# microm_schem2.net
KiCad netlist of a schematic drawn in EAGLE
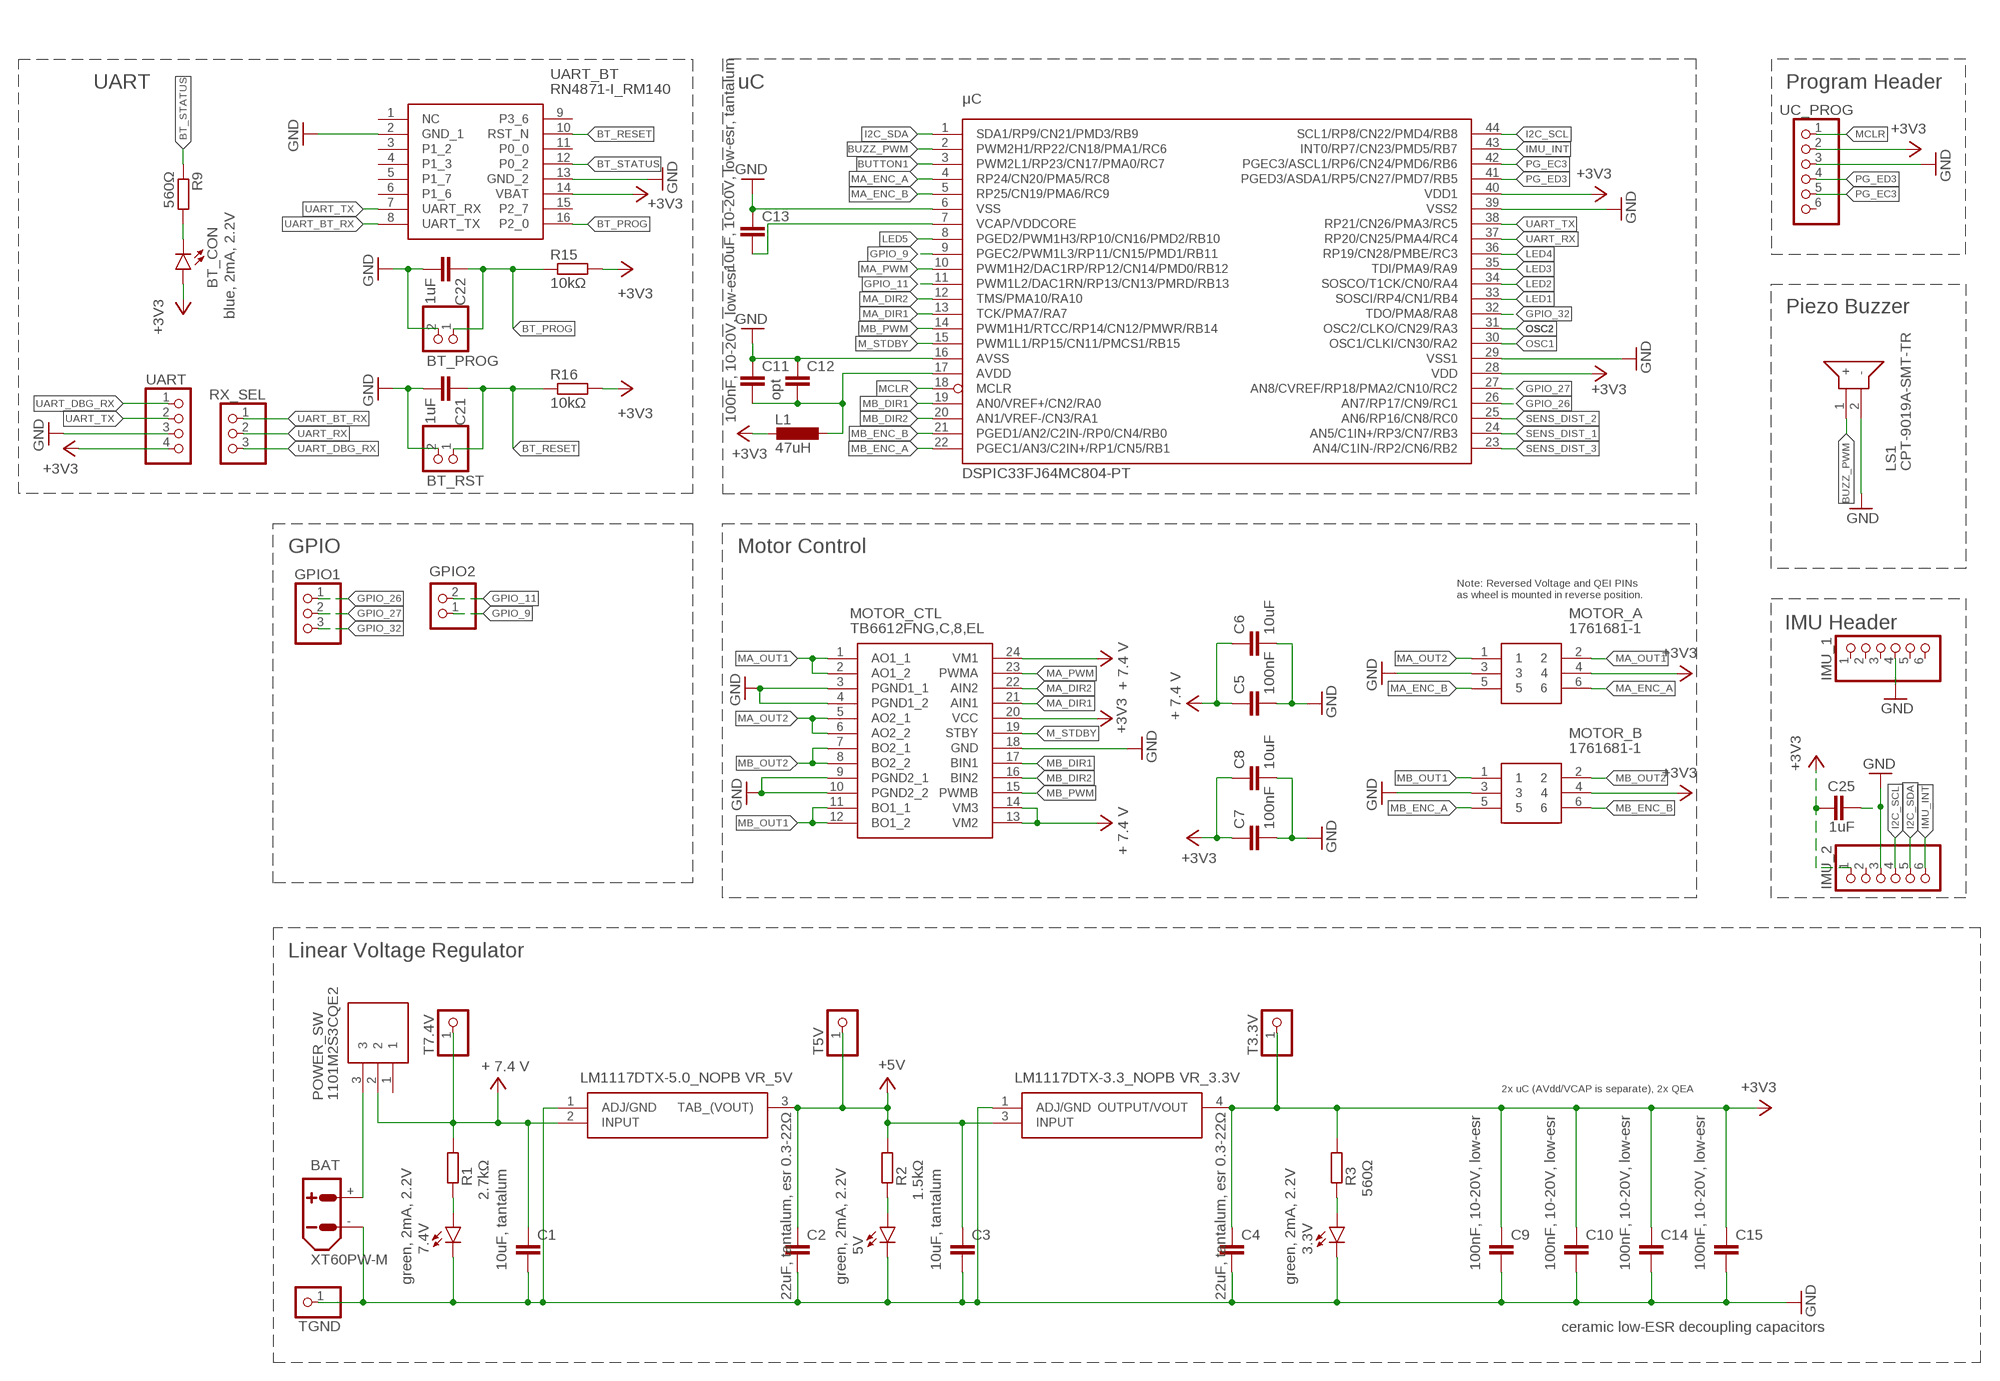
[diagram p0: schematic, sheet 1, part 1 of 2]
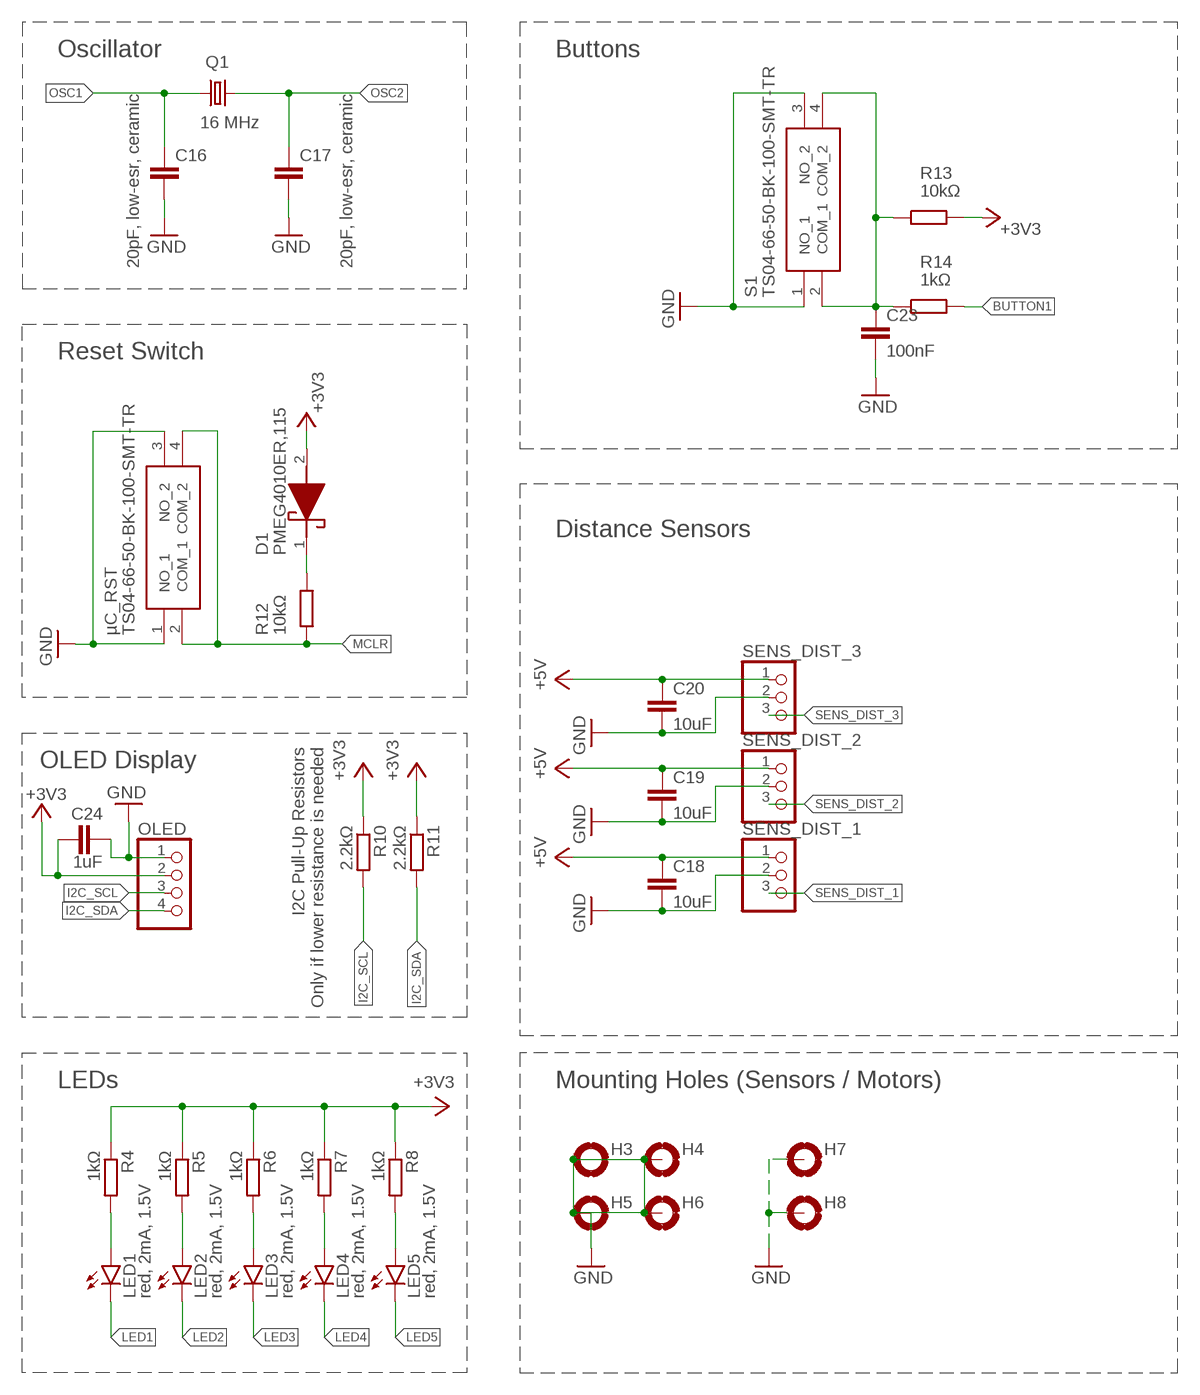
[diagram p1: schematic, sheet 1, part 2 of 2]

(export (version "E")
  (design (tool "Eeschema 10.0.6"))
  (components
    (comp (ref "3.3V")
      (value "green, 2mA, 2.2V")
      (footprint "eagle-import:CHIP-LED0805")
      (libsource (lib "eagle-import") (part "LEDCHIP-LED0805"))
    )
    (comp (ref "5V")
      (value "green, 2mA, 2.2V")
      (footprint "eagle-import:CHIP-LED0805")
      (libsource (lib "eagle-import") (part "LEDCHIP-LED0805"))
    )
    (comp (ref "7.4V")
      (value "green, 2mA, 2.2V")
      (footprint "eagle-import:CHIP-LED0805")
      (libsource (lib "eagle-import") (part "LEDCHIP-LED0805"))
    )
    (comp (ref "BAT")
      (value "XT60PW-M")
      (footprint "eagle-import:XT60PW-M")
      (libsource (lib "eagle-import") (part "XT60PW-M"))
    )
    (comp (ref "BT_CON")
      (value "blue, 2mA, 2.2V")
      (footprint "eagle-import:CHIP-LED0805")
      (libsource (lib "eagle-import") (part "LEDCHIP-LED0805"))
    )
    (comp (ref "BT_PROG")
      (value "PINHD-1X2")
      (footprint "eagle-import:1X02")
      (libsource (lib "eagle-import") (part "PINHD-1X2"))
    )
    (comp (ref "BT_RST")
      (value "PINHD-1X2")
      (footprint "eagle-import:1X02")
      (libsource (lib "eagle-import") (part "PINHD-1X2"))
    )
    (comp (ref "C1")
      (value "10uF, tantalum")
      (footprint "eagle-import:C0805")
      (libsource (lib "eagle-import") (part "C-EUC0805"))
    )
    (comp (ref "C2")
      (value "22uF, tantalum, esr 0.3-22Ω")
      (footprint "eagle-import:C0805")
      (libsource (lib "eagle-import") (part "C-EUC0805"))
    )
    (comp (ref "C3")
      (value "10uF, tantalum")
      (footprint "eagle-import:C0805")
      (libsource (lib "eagle-import") (part "C-EUC0805"))
    )
    (comp (ref "C4")
      (value "22uF, tantalum, esr 0.3-22Ω")
      (footprint "eagle-import:C0805")
      (libsource (lib "eagle-import") (part "C-EUC0805"))
    )
    (comp (ref "C5")
      (value "100nF")
      (footprint "eagle-import:C0805")
      (libsource (lib "eagle-import") (part "C-EUC0805"))
    )
    (comp (ref "C6")
      (value "10uF")
      (footprint "eagle-import:C0805")
      (libsource (lib "eagle-import") (part "C-EUC0805"))
    )
    (comp (ref "C7")
      (value "100nF")
      (footprint "eagle-import:C0805")
      (libsource (lib "eagle-import") (part "C-EUC0805"))
    )
    (comp (ref "C8")
      (value "10uF")
      (footprint "eagle-import:C0805")
      (libsource (lib "eagle-import") (part "C-EUC0805"))
    )
    (comp (ref "C9")
      (value "100nF, 10-20V, low-esr")
      (footprint "eagle-import:C0805")
      (libsource (lib "eagle-import") (part "C-EUC0805"))
    )
    (comp (ref "C10")
      (value "100nF, 10-20V, low-esr")
      (footprint "eagle-import:C0805")
      (libsource (lib "eagle-import") (part "C-EUC0805"))
    )
    (comp (ref "C11")
      (value "100nF, 10-20V, low-esr")
      (footprint "eagle-import:C0805")
      (libsource (lib "eagle-import") (part "C-EUC0805"))
    )
    (comp (ref "C12")
      (value "opt")
      (footprint "eagle-import:C0805")
      (libsource (lib "eagle-import") (part "C-EUC0805"))
    )
    (comp (ref "C13")
      (value "10uF, 10-20V, low-esr, tantalum")
      (footprint "eagle-import:C0805")
      (libsource (lib "eagle-import") (part "C-EUC0805"))
    )
    (comp (ref "C14")
      (value "100nF, 10-20V, low-esr")
      (footprint "eagle-import:C0805")
      (libsource (lib "eagle-import") (part "C-EUC0805"))
    )
    (comp (ref "C15")
      (value "100nF, 10-20V, low-esr")
      (footprint "eagle-import:C0805")
      (libsource (lib "eagle-import") (part "C-EUC0805"))
    )
    (comp (ref "C16")
      (value "20pF, low-esr, ceramic")
      (footprint "eagle-import:C0805")
      (libsource (lib "eagle-import") (part "C-EUC0805"))
    )
    (comp (ref "C17")
      (value "20pF, low-esr, ceramic")
      (footprint "eagle-import:C0805")
      (libsource (lib "eagle-import") (part "C-EUC0805"))
    )
    (comp (ref "C18")
      (value "10uF")
      (footprint "eagle-import:C0805")
      (libsource (lib "eagle-import") (part "C-EUC0805"))
    )
    (comp (ref "C19")
      (value "10uF")
      (footprint "eagle-import:C0805")
      (libsource (lib "eagle-import") (part "C-EUC0805"))
    )
    (comp (ref "C20")
      (value "10uF")
      (footprint "eagle-import:C0805")
      (libsource (lib "eagle-import") (part "C-EUC0805"))
    )
    (comp (ref "C21")
      (value "1uF")
      (footprint "eagle-import:C0805")
      (libsource (lib "eagle-import") (part "C-EUC0805"))
    )
    (comp (ref "C22")
      (value "1uF")
      (footprint "eagle-import:C0805")
      (libsource (lib "eagle-import") (part "C-EUC0805"))
    )
    (comp (ref "C23")
      (value "100nF")
      (footprint "eagle-import:C0805")
      (libsource (lib "eagle-import") (part "C-EUC0805"))
    )
    (comp (ref "C24")
      (value "1uF")
      (footprint "eagle-import:C0805")
      (libsource (lib "eagle-import") (part "C-EUC0805"))
    )
    (comp (ref "C25")
      (value "1uF")
      (footprint "eagle-import:C0805")
      (libsource (lib "eagle-import") (part "C-EUC0805"))
    )
    (comp (ref "D1")
      (value "PMEG4010ER,115")
      (footprint "eagle-import:PMEG4010ER115")
      (fields (field (name "MOUSER_PART_NUMBER") "771-PMEG4010ER115"))
      (libsource (lib "eagle-import") (part "PMEG4010ER,115"))
    )
    (comp (ref "GPIO1")
      (value "PINHD-1X3")
      (footprint "eagle-import:1X03")
      (libsource (lib "eagle-import") (part "PINHD-1X3"))
    )
    (comp (ref "GPIO2")
      (value "PINHD-1X2")
      (footprint "eagle-import:1X02")
      (libsource (lib "eagle-import") (part "PINHD-1X2"))
    )
    (comp (ref "H3")
      (value "MOUNT-PAD-ROUND2.8")
      (footprint "eagle-import:2,8-PAD")
      (libsource (lib "eagle-import") (part "MOUNT-PAD-ROUND2.8"))
    )
    (comp (ref "H4")
      (value "MOUNT-PAD-ROUND2.8")
      (footprint "eagle-import:2,8-PAD")
      (libsource (lib "eagle-import") (part "MOUNT-PAD-ROUND2.8"))
    )
    (comp (ref "H5")
      (value "MOUNT-PAD-ROUND2.8")
      (footprint "eagle-import:2,8-PAD")
      (libsource (lib "eagle-import") (part "MOUNT-PAD-ROUND2.8"))
    )
    (comp (ref "H6")
      (value "MOUNT-PAD-ROUND2.8")
      (footprint "eagle-import:2,8-PAD")
      (libsource (lib "eagle-import") (part "MOUNT-PAD-ROUND2.8"))
    )
    (comp (ref "H7")
      (value "MOUNT-PAD-ROUND2.8")
      (footprint "eagle-import:2,8-PAD")
      (libsource (lib "eagle-import") (part "MOUNT-PAD-ROUND2.8"))
    )
    (comp (ref "H8")
      (value "MOUNT-PAD-ROUND2.8")
      (footprint "eagle-import:2,8-PAD")
      (libsource (lib "eagle-import") (part "MOUNT-PAD-ROUND2.8"))
    )
    (comp (ref "IMU_1")
      (value "PINHD-1X6")
      (footprint "eagle-import:1X06")
      (libsource (lib "eagle-import") (part "PINHD-1X6"))
    )
    (comp (ref "IMU_2")
      (value "PINHD-1X6")
      (footprint "eagle-import:1X06")
      (libsource (lib "eagle-import") (part "PINHD-1X6"))
    )
    (comp (ref "L1")
      (value "47uH")
      (footprint "eagle-import:L1812")
      (libsource (lib "eagle-import") (part "L-EUL1812"))
    )
    (comp (ref "LED1")
      (value "red, 2mA, 1.5V")
      (footprint "eagle-import:CHIPLED_0805")
      (libsource (lib "eagle-import") (part "LEDCHIPLED_0805"))
    )
    (comp (ref "LED2")
      (value "red, 2mA, 1.5V")
      (footprint "eagle-import:CHIPLED_0805")
      (libsource (lib "eagle-import") (part "LEDCHIPLED_0805"))
    )
    (comp (ref "LED3")
      (value "red, 2mA, 1.5V")
      (footprint "eagle-import:CHIPLED_0805")
      (libsource (lib "eagle-import") (part "LEDCHIPLED_0805"))
    )
    (comp (ref "LED4")
      (value "red, 2mA, 1.5V")
      (footprint "eagle-import:CHIPLED_0805")
      (libsource (lib "eagle-import") (part "LEDCHIPLED_0805"))
    )
    (comp (ref "LED5")
      (value "red, 2mA, 1.5V")
      (footprint "eagle-import:CHIPLED_0805")
      (libsource (lib "eagle-import") (part "LEDCHIPLED_0805"))
    )
    (comp (ref "LS1")
      (value "CPT-9019A-SMT-TR")
      (footprint "eagle-import:CPT9019ASMTTR")
      (fields (field (name "MOUSER_PART_NUMBER") "179-CPT-9019A-SMT-TR"))
      (libsource (lib "eagle-import") (part "CPT-9019A-SMT-TR"))
    )
    (comp (ref "MOTOR_A")
      (value "1761681-1")
      (footprint "eagle-import:SHDR6W67P254_2X3_1524X916X922P")
      (fields (field (name "MOUSER_PART_NUMBER") "571-1761681-1"))
      (libsource (lib "eagle-import") (part "1761681-1"))
    )
    (comp (ref "MOTOR_B")
      (value "1761681-1")
      (footprint "eagle-import:SHDR6W67P254_2X3_1524X916X922P")
      (fields (field (name "MOUSER_PART_NUMBER") "571-1761681-1"))
      (libsource (lib "eagle-import") (part "1761681-1"))
    )
    (comp (ref "MOTOR_CTL")
      (value "TB6612FNG,C,8,EL")
      (footprint "eagle-import:SOP65P760X160-24N")
      (fields (field (name "MOUSER_PART_NUMBER") "757-TB6612FNGC8EL"))
      (libsource (lib "eagle-import") (part "TB6612FNG,C,8,EL"))
    )
    (comp (ref "OLED")
      (value "PINHD-1X4")
      (footprint "eagle-import:1X04")
      (libsource (lib "eagle-import") (part "PINHD-1X4"))
    )
    (comp (ref "POWER_SW")
      (value "1101M2S3CQE2")
      (footprint "eagle-import:1000-SERIES(SPDT)")
      (fields (field (name "MOUSER_PART_NUMBER") "611-1101M2S3CQE2"))
      (libsource (lib "eagle-import") (part "1101M2S3CQE2"))
    )
    (comp (ref "Q1")
      (value "16 MHz")
      (footprint "eagle-import:HC49_S")
      (libsource (lib "eagle-import") (part "CRYSTALHC49S"))
    )
    (comp (ref "R1")
      (value "2.7kΩ")
      (footprint "eagle-import:R0805")
      (libsource (lib "eagle-import") (part "R-EU_R0805"))
    )
    (comp (ref "R2")
      (value "1.5kΩ")
      (footprint "eagle-import:R0805")
      (libsource (lib "eagle-import") (part "R-EU_R0805"))
    )
    (comp (ref "R3")
      (value "560Ω")
      (footprint "eagle-import:R0805")
      (libsource (lib "eagle-import") (part "R-EU_R0805"))
    )
    (comp (ref "R4")
      (value "1kΩ")
      (footprint "eagle-import:R0805")
      (libsource (lib "eagle-import") (part "R-EU_R0805"))
    )
    (comp (ref "R5")
      (value "1kΩ")
      (footprint "eagle-import:R0805")
      (libsource (lib "eagle-import") (part "R-EU_R0805"))
    )
    (comp (ref "R6")
      (value "1kΩ")
      (footprint "eagle-import:R0805")
      (libsource (lib "eagle-import") (part "R-EU_R0805"))
    )
    (comp (ref "R7")
      (value "1kΩ")
      (footprint "eagle-import:R0805")
      (libsource (lib "eagle-import") (part "R-EU_R0805"))
    )
    (comp (ref "R8")
      (value "1kΩ")
      (footprint "eagle-import:R0805")
      (libsource (lib "eagle-import") (part "R-EU_R0805"))
    )
    (comp (ref "R9")
      (value "560Ω")
      (footprint "eagle-import:R0805")
      (libsource (lib "eagle-import") (part "R-EU_R0805"))
    )
    (comp (ref "R10")
      (value "2.2kΩ")
      (footprint "eagle-import:R0805")
      (libsource (lib "eagle-import") (part "R-EU_R0805"))
    )
    (comp (ref "R11")
      (value "2.2kΩ")
      (footprint "eagle-import:R0805")
      (libsource (lib "eagle-import") (part "R-EU_R0805"))
    )
    (comp (ref "R12")
      (value "10kΩ")
      (footprint "eagle-import:R0805")
      (libsource (lib "eagle-import") (part "R-EU_R0805"))
    )
    (comp (ref "R13")
      (value "10kΩ")
      (footprint "eagle-import:R0805")
      (libsource (lib "eagle-import") (part "R-EU_R0805"))
    )
    (comp (ref "R14")
      (value "1kΩ")
      (footprint "eagle-import:R0805")
      (libsource (lib "eagle-import") (part "R-EU_R0805"))
    )
    (comp (ref "R15")
      (value "10kΩ")
      (footprint "eagle-import:R0805")
      (libsource (lib "eagle-import") (part "R-EU_R0805"))
    )
    (comp (ref "R16")
      (value "10kΩ")
      (footprint "eagle-import:R0805")
      (libsource (lib "eagle-import") (part "R-EU_R0805"))
    )
    (comp (ref "RX_SEL")
      (value "PINHD-1X3")
      (footprint "eagle-import:1X03")
      (libsource (lib "eagle-import") (part "PINHD-1X3"))
    )
    (comp (ref "S1")
      (value "TS04-66-50-BK-100-SMT-TR")
      (footprint "eagle-import:TS046650BK100SMTTR")
      (fields
        (field (name "MANUFACTURER_PART_NUMBER") "TS04-66-95-BK-160-SMT-TR")
        (field (name "MOUSER_PART_NUMBER") "179-TS046695BK160SMR")
      )
      (libsource (lib "eagle-import") (part "TS04-66-50-BK-100-SMT-TR"))
    )
    (comp (ref "SENS_DIST_1")
      (value "PINHD-1X3")
      (footprint "eagle-import:1X03")
      (libsource (lib "eagle-import") (part "PINHD-1X3"))
    )
    (comp (ref "SENS_DIST_2")
      (value "PINHD-1X3")
      (footprint "eagle-import:1X03")
      (libsource (lib "eagle-import") (part "PINHD-1X3"))
    )
    (comp (ref "SENS_DIST_3")
      (value "PINHD-1X3")
      (footprint "eagle-import:1X03")
      (libsource (lib "eagle-import") (part "PINHD-1X3"))
    )
    (comp (ref "T3.3V")
      (value "PINHD-1X1")
      (footprint "eagle-import:1X01")
      (libsource (lib "eagle-import") (part "PINHD-1X1"))
    )
    (comp (ref "T5V")
      (value "PINHD-1X1")
      (footprint "eagle-import:1X01")
      (libsource (lib "eagle-import") (part "PINHD-1X1"))
    )
    (comp (ref "T7.4V")
      (value "PINHD-1X1")
      (footprint "eagle-import:1X01")
      (libsource (lib "eagle-import") (part "PINHD-1X1"))
    )
    (comp (ref "TGND")
      (value "PINHD-1X1")
      (footprint "eagle-import:1X01")
      (libsource (lib "eagle-import") (part "PINHD-1X1"))
    )
    (comp (ref "UART")
      (value "PINHD-1X4")
      (footprint "eagle-import:1X04")
      (libsource (lib "eagle-import") (part "PINHD-1X4"))
    )
    (comp (ref "UART_BT")
      (value "RN4871-I_RM140")
      (footprint "eagle-import:RN4871IRM140")
      (fields
        (field (name "ARROW_PART_NUMBER") "RN4871-I/RM140")
        (field (name "MOUSER_PART_NUMBER") "579-RN4871-I/RM140")
      )
      (libsource (lib "eagle-import") (part "RN4871-I_RM140"))
    )
    (comp (ref "UC_PROG")
      (value "PINHD-1X6")
      (footprint "eagle-import:1X06")
      (libsource (lib "eagle-import") (part "PINHD-1X6"))
    )
    (comp (ref "VR_3.3V")
      (value "LM1117DTX-3.3_NOPB")
      (footprint "eagle-import:LM1117DTX33NOPB")
      (fields
        (field (name "ARROW_PART_NUMBER") "LM1117DTX-3.3/NOPB")
        (field (name "MOUSER_PART_NUMBER") "926-LM1117DTX3.3NOPB")
      )
      (libsource (lib "eagle-import") (part "LM1117DTX-3.3_NOPB"))
    )
    (comp (ref "VR_5V")
      (value "LM1117DTX-5.0_NOPB")
      (footprint "eagle-import:LM78M05CDT")
      (fields
        (field (name "ARROW_PART_NUMBER") "LM1117DTX-5.0/NOPB")
        (field (name "MOUSER_PART_NUMBER") "926-LM1117DTX50NOPB")
      )
      (libsource (lib "eagle-import") (part "LM1117DTX-5.0_NOPB"))
    )
    (comp (ref "μC")
      (value "DSPIC33FJ64MC804-PT")
      (footprint "eagle-import:TQFP44")
      (libsource (lib "eagle-import") (part "DSPIC33FJ64MC804-PT"))
    )
    (comp (ref "µC_RST")
      (value "TS04-66-50-BK-100-SMT-TR")
      (footprint "eagle-import:TS046650BK100SMTTR")
      (fields
        (field (name "MANUFACTURER_PART_NUMBER") "TS04-66-95-BK-160-SMT-TR")
        (field (name "MOUSER_PART_NUMBER") "179-TS046695BK160SMR")
      )
      (libsource (lib "eagle-import") (part "TS04-66-50-BK-100-SMT-TR"))
    )
  )
  (nets
    (net (code "1") (name "+ 7.4 V") (class "Default")
      (node (ref "C1") (pin "1") (pinfunction "1_1") (pintype "passive"))
      (node (ref "C5") (pin "1") (pinfunction "1_1") (pintype "passive"))
      (node (ref "C6") (pin "1") (pinfunction "1_1") (pintype "passive"))
      (node (ref "MOTOR_CTL") (pin "13") (pinfunction "VM2_13") (pintype "bidirectional"))
      (node (ref "MOTOR_CTL") (pin "14") (pinfunction "VM3_14") (pintype "bidirectional"))
      (node (ref "MOTOR_CTL") (pin "24") (pinfunction "VM1_24") (pintype "bidirectional"))
      (node (ref "POWER_SW") (pin "2") (pinfunction "2_2") (pintype "bidirectional"))
      (node (ref "R1") (pin "1") (pinfunction "1_1") (pintype "passive"))
      (node (ref "T7.4V") (pin "1") (pinfunction "1_1") (pintype "passive"))
      (node (ref "VR_5V") (pin "2") (pinfunction "INPUT_2") (pintype "bidirectional"))
    )
    (net (code "2") (name "+3V3") (class "Default")
      (node (ref "BT_CON") (pin "A") (pinfunction "A_A") (pintype "passive"))
      (node (ref "C10") (pin "1") (pinfunction "1_1") (pintype "passive"))
      (node (ref "C14") (pin "1") (pinfunction "1_1") (pintype "passive"))
      (node (ref "C15") (pin "1") (pinfunction "1_1") (pintype "passive"))
      (node (ref "C24") (pin "1") (pinfunction "1_1") (pintype "passive"))
      (node (ref "C25") (pin "1") (pinfunction "1_1") (pintype "passive"))
      (node (ref "C4") (pin "1") (pinfunction "1_1") (pintype "passive"))
      (node (ref "C7") (pin "1") (pinfunction "1_1") (pintype "passive"))
      (node (ref "C8") (pin "1") (pinfunction "1_1") (pintype "passive"))
      (node (ref "C9") (pin "1") (pinfunction "1_1") (pintype "passive"))
      (node (ref "D1") (pin "2") (pinfunction "A_2") (pintype "bidirectional"))
      (node (ref "IMU_2") (pin "1") (pinfunction "1_1") (pintype "passive"))
      (node (ref "L1") (pin "2") (pinfunction "2_2") (pintype "passive"))
      (node (ref "MOTOR_A") (pin "4") (pinfunction "4_4") (pintype "bidirectional"))
      (node (ref "MOTOR_B") (pin "4") (pinfunction "4_4") (pintype "bidirectional"))
      (node (ref "MOTOR_CTL") (pin "20") (pinfunction "VCC_20") (pintype "bidirectional"))
      (node (ref "OLED") (pin "2") (pinfunction "2_2") (pintype "passive"))
      (node (ref "R10") (pin "1") (pinfunction "1_1") (pintype "passive"))
      (node (ref "R11") (pin "1") (pinfunction "1_1") (pintype "passive"))
      (node (ref "R13") (pin "2") (pinfunction "2_2") (pintype "passive"))
      (node (ref "R15") (pin "2") (pinfunction "2_2") (pintype "passive"))
      (node (ref "R16") (pin "2") (pinfunction "2_2") (pintype "passive"))
      (node (ref "R3") (pin "1") (pinfunction "1_1") (pintype "passive"))
      (node (ref "R4") (pin "1") (pinfunction "1_1") (pintype "passive"))
      (node (ref "R5") (pin "1") (pinfunction "1_1") (pintype "passive"))
      (node (ref "R6") (pin "1") (pinfunction "1_1") (pintype "passive"))
      (node (ref "R7") (pin "1") (pinfunction "1_1") (pintype "passive"))
      (node (ref "R8") (pin "1") (pinfunction "1_1") (pintype "passive"))
      (node (ref "T3.3V") (pin "1") (pinfunction "1_1") (pintype "passive"))
      (node (ref "UART") (pin "4") (pinfunction "4_4") (pintype "passive"))
      (node (ref "UART_BT") (pin "14") (pinfunction "VBAT_14") (pintype "bidirectional"))
      (node (ref "UC_PROG") (pin "2") (pinfunction "2_2") (pintype "passive"))
      (node (ref "VR_3.3V") (pin "4") (pinfunction "OUTPUT/VOUT_4") (pintype "bidirectional"))
      (node (ref "μC") (pin "28") (pinfunction "VDD_28") (pintype "power_in"))
      (node (ref "μC") (pin "40") (pinfunction "VDD1_40") (pintype "power_in"))
    )
    (net (code "3") (name "+5V") (class "Default")
      (node (ref "C18") (pin "1") (pinfunction "1_1") (pintype "passive"))
      (node (ref "C19") (pin "1") (pinfunction "1_1") (pintype "passive"))
      (node (ref "C2") (pin "1") (pinfunction "1_1") (pintype "passive"))
      (node (ref "C20") (pin "1") (pinfunction "1_1") (pintype "passive"))
      (node (ref "C3") (pin "1") (pinfunction "1_1") (pintype "passive"))
      (node (ref "R2") (pin "1") (pinfunction "1_1") (pintype "passive"))
      (node (ref "SENS_DIST_1") (pin "1") (pinfunction "1_1") (pintype "passive"))
      (node (ref "SENS_DIST_2") (pin "1") (pinfunction "1_1") (pintype "passive"))
      (node (ref "SENS_DIST_3") (pin "1") (pinfunction "1_1") (pintype "passive"))
      (node (ref "T5V") (pin "1") (pinfunction "1_1") (pintype "passive"))
      (node (ref "VR_3.3V") (pin "3") (pinfunction "INPUT_3") (pintype "bidirectional"))
      (node (ref "VR_5V") (pin "3") (pinfunction "TAB_(VOUT)_3") (pintype "bidirectional"))
    )
    (net (code "4") (name "BT_PROG") (class "Default")
      (node (ref "BT_PROG") (pin "1") (pinfunction "1_1") (pintype "passive"))
      (node (ref "C22") (pin "1") (pinfunction "1_1") (pintype "passive"))
      (node (ref "R15") (pin "1") (pinfunction "1_1") (pintype "passive"))
      (node (ref "UART_BT") (pin "16") (pinfunction "P2_0_16") (pintype "bidirectional"))
    )
    (net (code "5") (name "BT_RESET") (class "Default")
      (node (ref "BT_RST") (pin "1") (pinfunction "1_1") (pintype "passive"))
      (node (ref "C21") (pin "1") (pinfunction "1_1") (pintype "passive"))
      (node (ref "R16") (pin "1") (pinfunction "1_1") (pintype "passive"))
      (node (ref "UART_BT") (pin "10") (pinfunction "RST_N_10") (pintype "bidirectional"))
    )
    (net (code "6") (name "BT_STATUS") (class "Default")
      (node (ref "R9") (pin "1") (pinfunction "1_1") (pintype "passive"))
      (node (ref "UART_BT") (pin "12") (pinfunction "P0_2_12") (pintype "bidirectional"))
    )
    (net (code "7") (name "BUTTON1") (class "Default")
      (node (ref "R14") (pin "2") (pinfunction "2_2") (pintype "passive"))
      (node (ref "μC") (pin "3") (pinfunction "PWM2L1/RP23/CN17/PMA0/RC7_3") (pintype "bidirectional"))
    )
    (net (code "8") (name "BUZZ_PWM") (class "Default")
      (node (ref "LS1") (pin "1") (pinfunction "+_1") (pintype "bidirectional"))
      (node (ref "μC") (pin "2") (pinfunction "PWM2H1/RP22/CN18/PMA1/RC6_2") (pintype "bidirectional"))
    )
    (net (code "9") (name "GND") (class "Default")
      (node (ref "3.3V") (pin "C") (pinfunction "C_C") (pintype "passive"))
      (node (ref "5V") (pin "C") (pinfunction "C_C") (pintype "passive"))
      (node (ref "7.4V") (pin "C") (pinfunction "C_C") (pintype "passive"))
      (node (ref "BAT") (pin "-") (pinfunction "-_-") (pintype "power_in"))
      (node (ref "BT_PROG") (pin "2") (pinfunction "2_2") (pintype "passive"))
      (node (ref "BT_RST") (pin "2") (pinfunction "2_2") (pintype "passive"))
      (node (ref "C1") (pin "2") (pinfunction "2_2") (pintype "passive"))
      (node (ref "C10") (pin "2") (pinfunction "2_2") (pintype "passive"))
      (node (ref "C11") (pin "1") (pinfunction "1_1") (pintype "passive"))
      (node (ref "C12") (pin "1") (pinfunction "1_1") (pintype "passive"))
      (node (ref "C13") (pin "1") (pinfunction "1_1") (pintype "passive"))
      (node (ref "C14") (pin "2") (pinfunction "2_2") (pintype "passive"))
      (node (ref "C15") (pin "2") (pinfunction "2_2") (pintype "passive"))
      (node (ref "C16") (pin "2") (pinfunction "2_2") (pintype "passive"))
      (node (ref "C17") (pin "2") (pinfunction "2_2") (pintype "passive"))
      (node (ref "C18") (pin "2") (pinfunction "2_2") (pintype "passive"))
      (node (ref "C19") (pin "2") (pinfunction "2_2") (pintype "passive"))
      (node (ref "C2") (pin "2") (pinfunction "2_2") (pintype "passive"))
      (node (ref "C20") (pin "2") (pinfunction "2_2") (pintype "passive"))
      (node (ref "C21") (pin "2") (pinfunction "2_2") (pintype "passive"))
      (node (ref "C22") (pin "2") (pinfunction "2_2") (pintype "passive"))
      (node (ref "C23") (pin "2") (pinfunction "2_2") (pintype "passive"))
      (node (ref "C24") (pin "2") (pinfunction "2_2") (pintype "passive"))
      (node (ref "C25") (pin "2") (pinfunction "2_2") (pintype "passive"))
      (node (ref "C3") (pin "2") (pinfunction "2_2") (pintype "passive"))
      (node (ref "C4") (pin "2") (pinfunction "2_2") (pintype "passive"))
      (node (ref "C5") (pin "2") (pinfunction "2_2") (pintype "passive"))
      (node (ref "C6") (pin "2") (pinfunction "2_2") (pintype "passive"))
      (node (ref "C7") (pin "2") (pinfunction "2_2") (pintype "passive"))
      (node (ref "C8") (pin "2") (pinfunction "2_2") (pintype "passive"))
      (node (ref "C9") (pin "2") (pinfunction "2_2") (pintype "passive"))
      (node (ref "H3") (pin "B2,8") (pinfunction "MOUNT_B2,8") (pintype "passive"))
      (node (ref "H4") (pin "B2,8") (pinfunction "MOUNT_B2,8") (pintype "passive"))
      (node (ref "H5") (pin "B2,8") (pinfunction "MOUNT_B2,8") (pintype "passive"))
      (node (ref "H6") (pin "B2,8") (pinfunction "MOUNT_B2,8") (pintype "passive"))
      (node (ref "H7") (pin "B2,8") (pinfunction "MOUNT_B2,8") (pintype "passive"))
      (node (ref "H8") (pin "B2,8") (pinfunction "MOUNT_B2,8") (pintype "passive"))
      (node (ref "IMU_1") (pin "4") (pinfunction "4_4") (pintype "passive"))
      (node (ref "IMU_2") (pin "3") (pinfunction "3_3") (pintype "passive"))
      (node (ref "LS1") (pin "2") (pinfunction "-_2") (pintype "bidirectional"))
      (node (ref "MOTOR_A") (pin "3") (pinfunction "3_3") (pintype "bidirectional"))
      (node (ref "MOTOR_B") (pin "3") (pinfunction "3_3") (pintype "bidirectional"))
      (node (ref "MOTOR_CTL") (pin "10") (pinfunction "PGND2_2_10") (pintype "bidirectional"))
      (node (ref "MOTOR_CTL") (pin "18") (pinfunction "GND_18") (pintype "bidirectional"))
      (node (ref "MOTOR_CTL") (pin "3") (pinfunction "PGND1_1_3") (pintype "bidirectional"))
      (node (ref "MOTOR_CTL") (pin "4") (pinfunction "PGND1_2_4") (pintype "bidirectional"))
      (node (ref "MOTOR_CTL") (pin "9") (pinfunction "PGND2_1_9") (pintype "bidirectional"))
      (node (ref "OLED") (pin "1") (pinfunction "1_1") (pintype "passive"))
      (node (ref "S1") (pin "1") (pinfunction "NO_1_1") (pintype "bidirectional"))
      (node (ref "S1") (pin "3") (pinfunction "NO_2_3") (pintype "bidirectional"))
      (node (ref "SENS_DIST_1") (pin "2") (pinfunction "2_2") (pintype "passive"))
      (node (ref "SENS_DIST_2") (pin "2") (pinfunction "2_2") (pintype "passive"))
      (node (ref "SENS_DIST_3") (pin "2") (pinfunction "2_2") (pintype "passive"))
      (node (ref "TGND") (pin "1") (pinfunction "1_1") (pintype "passive"))
      (node (ref "UART") (pin "3") (pinfunction "3_3") (pintype "passive"))
      (node (ref "UART_BT") (pin "13") (pinfunction "GND_2_13") (pintype "bidirectional"))
      (node (ref "UART_BT") (pin "2") (pinfunction "GND_1_2") (pintype "bidirectional"))
      (node (ref "UC_PROG") (pin "3") (pinfunction "3_3") (pintype "passive"))
      (node (ref "VR_3.3V") (pin "1") (pinfunction "ADJ/GND_1") (pintype "bidirectional"))
      (node (ref "VR_5V") (pin "1") (pinfunction "ADJ/GND_1") (pintype "bidirectional"))
      (node (ref "µC_RST") (pin "1") (pinfunction "NO_1_1") (pintype "bidirectional"))
      (node (ref "µC_RST") (pin "3") (pinfunction "NO_2_3") (pintype "bidirectional"))
      (node (ref "μC") (pin "16") (pinfunction "AVSS_16") (pintype "power_in"))
      (node (ref "μC") (pin "29") (pinfunction "VSS1_29") (pintype "power_in"))
      (node (ref "μC") (pin "39") (pinfunction "VSS2_39") (pintype "power_in"))
      (node (ref "μC") (pin "6") (pinfunction "VSS_6") (pintype "power_in"))
    )
    (net (code "10") (name "GPIO_9") (class "Default")
      (node (ref "GPIO2") (pin "1") (pinfunction "1_1") (pintype "passive"))
      (node (ref "μC") (pin "9") (pinfunction "PGEC2/PWM1L3/RP11/CN15/PMD1/RB11_9") (pintype "bidirectional"))
    )
    (net (code "11") (name "GPIO_11") (class "Default")
      (node (ref "GPIO2") (pin "2") (pinfunction "2_2") (pintype "passive"))
      (node (ref "μC") (pin "11") (pinfunction "PWM1L2/DAC1RN/RP13/CN13/PMRD/RB13_11") (pintype "bidirectional"))
    )
    (net (code "12") (name "GPIO_26") (class "Default")
      (node (ref "GPIO1") (pin "1") (pinfunction "1_1") (pintype "passive"))
      (node (ref "μC") (pin "26") (pinfunction "AN7/RP17/CN9/RC1_26") (pintype "bidirectional"))
    )
    (net (code "13") (name "GPIO_27") (class "Default")
      (node (ref "GPIO1") (pin "2") (pinfunction "2_2") (pintype "passive"))
      (node (ref "μC") (pin "27") (pinfunction "AN8/CVREF/RP18/PMA2/CN10/RC2_27") (pintype "bidirectional"))
    )
    (net (code "14") (name "GPIO_32") (class "Default")
      (node (ref "GPIO1") (pin "3") (pinfunction "3_3") (pintype "passive"))
      (node (ref "μC") (pin "32") (pinfunction "TDO/PMA8/RA8_32") (pintype "bidirectional"))
    )
    (net (code "15") (name "I2C_SCL") (class "Default")
      (node (ref "IMU_2") (pin "4") (pinfunction "4_4") (pintype "passive"))
      (node (ref "OLED") (pin "3") (pinfunction "3_3") (pintype "passive"))
      (node (ref "R10") (pin "2") (pinfunction "2_2") (pintype "passive"))
      (node (ref "μC") (pin "44") (pinfunction "SCL1/RP8/CN22/PMD4/RB8_44") (pintype "bidirectional"))
    )
    (net (code "16") (name "I2C_SDA") (class "Default")
      (node (ref "IMU_2") (pin "5") (pinfunction "5_5") (pintype "passive"))
      (node (ref "OLED") (pin "4") (pinfunction "4_4") (pintype "passive"))
      (node (ref "R11") (pin "2") (pinfunction "2_2") (pintype "passive"))
      (node (ref "μC") (pin "1") (pinfunction "SDA1/RP9/CN21/PMD3/RB9_1") (pintype "bidirectional"))
    )
    (net (code "17") (name "IMU_INT") (class "Default")
      (node (ref "IMU_2") (pin "6") (pinfunction "6_6") (pintype "passive"))
      (node (ref "μC") (pin "43") (pinfunction "INT0/RP7/CN23/PMD5/RB7_43") (pintype "bidirectional"))
    )
    (net (code "18") (name "LED1") (class "Default")
      (node (ref "LED1") (pin "C") (pinfunction "C_C") (pintype "passive"))
      (node (ref "μC") (pin "33") (pinfunction "SOSCI/RP4/CN1/RB4_33") (pintype "bidirectional"))
    )
    (net (code "19") (name "LED2") (class "Default")
      (node (ref "LED2") (pin "C") (pinfunction "C_C") (pintype "passive"))
      (node (ref "μC") (pin "34") (pinfunction "SOSCO/T1CK/CN0/RA4_34") (pintype "bidirectional"))
    )
    (net (code "20") (name "LED3") (class "Default")
      (node (ref "LED3") (pin "C") (pinfunction "C_C") (pintype "passive"))
      (node (ref "μC") (pin "35") (pinfunction "TDI/PMA9/RA9_35") (pintype "bidirectional"))
    )
    (net (code "21") (name "LED4") (class "Default")
      (node (ref "LED4") (pin "C") (pinfunction "C_C") (pintype "passive"))
      (node (ref "μC") (pin "36") (pinfunction "RP19/CN28/PMBE/RC3_36") (pintype "bidirectional"))
    )
    (net (code "22") (name "LED5") (class "Default")
      (node (ref "LED5") (pin "C") (pinfunction "C_C") (pintype "passive"))
      (node (ref "μC") (pin "8") (pinfunction "PGED2/PWM1H3/RP10/CN16/PMD2/RB10_8") (pintype "bidirectional"))
    )
    (net (code "23") (name "MA_DIR1") (class "Default")
      (node (ref "MOTOR_CTL") (pin "21") (pinfunction "AIN1_21") (pintype "bidirectional"))
      (node (ref "μC") (pin "13") (pinfunction "TCK/PMA7/RA7_13") (pintype "bidirectional"))
    )
    (net (code "24") (name "MA_DIR2") (class "Default")
      (node (ref "MOTOR_CTL") (pin "22") (pinfunction "AIN2_22") (pintype "bidirectional"))
      (node (ref "μC") (pin "12") (pinfunction "TMS/PMA10/RA10_12") (pintype "bidirectional"))
    )
    (net (code "25") (name "MA_ENC_A") (class "Default")
      (node (ref "MOTOR_A") (pin "6") (pinfunction "6_6") (pintype "bidirectional"))
      (node (ref "μC") (pin "4") (pinfunction "RP24/CN20/PMA5/RC8_4") (pintype "bidirectional"))
    )
    (net (code "26") (name "MA_ENC_B") (class "Default")
      (node (ref "MOTOR_A") (pin "5") (pinfunction "5_5") (pintype "bidirectional"))
      (node (ref "μC") (pin "5") (pinfunction "RP25/CN19/PMA6/RC9_5") (pintype "bidirectional"))
    )
    (net (code "27") (name "MA_OUT1") (class "Default")
      (node (ref "MOTOR_A") (pin "2") (pinfunction "2_2") (pintype "bidirectional"))
      (node (ref "MOTOR_CTL") (pin "1") (pinfunction "AO1_1_1") (pintype "bidirectional"))
      (node (ref "MOTOR_CTL") (pin "2") (pinfunction "AO1_2_2") (pintype "bidirectional"))
    )
    (net (code "28") (name "MA_OUT2") (class "Default")
      (node (ref "MOTOR_A") (pin "1") (pinfunction "1_1") (pintype "bidirectional"))
      (node (ref "MOTOR_CTL") (pin "5") (pinfunction "AO2_1_5") (pintype "bidirectional"))
      (node (ref "MOTOR_CTL") (pin "6") (pinfunction "AO2_2_6") (pintype "bidirectional"))
    )
    (net (code "29") (name "MA_PWM") (class "Default")
      (node (ref "MOTOR_CTL") (pin "23") (pinfunction "PWMA_23") (pintype "bidirectional"))
      (node (ref "μC") (pin "10") (pinfunction "PWM1H2/DAC1RP/RP12/CN14/PMD0/RB12_10") (pintype "bidirectional"))
    )
    (net (code "30") (name "MB_DIR1") (class "Default")
      (node (ref "MOTOR_CTL") (pin "17") (pinfunction "BIN1_17") (pintype "bidirectional"))
      (node (ref "μC") (pin "19") (pinfunction "AN0/VREF+/CN2/RA0_19") (pintype "bidirectional"))
    )
    (net (code "31") (name "MB_DIR2") (class "Default")
      (node (ref "MOTOR_CTL") (pin "16") (pinfunction "BIN2_16") (pintype "bidirectional"))
      (node (ref "μC") (pin "20") (pinfunction "AN1/VREF-/CN3/RA1_20") (pintype "bidirectional"))
    )
    (net (code "32") (name "MB_ENC_A") (class "Default")
      (node (ref "MOTOR_B") (pin "5") (pinfunction "5_5") (pintype "bidirectional"))
      (node (ref "μC") (pin "22") (pinfunction "PGEC1/AN3/C2IN+/RP1/CN5/RB1_22") (pintype "bidirectional"))
    )
    (net (code "33") (name "MB_ENC_B") (class "Default")
      (node (ref "MOTOR_B") (pin "6") (pinfunction "6_6") (pintype "bidirectional"))
      (node (ref "μC") (pin "21") (pinfunction "PGED1/AN2/C2IN-/RP0/CN4/RB0_21") (pintype "bidirectional"))
    )
    (net (code "34") (name "MB_OUT1") (class "Default")
      (node (ref "MOTOR_B") (pin "1") (pinfunction "1_1") (pintype "bidirectional"))
      (node (ref "MOTOR_CTL") (pin "11") (pinfunction "BO1_1_11") (pintype "bidirectional"))
      (node (ref "MOTOR_CTL") (pin "12") (pinfunction "BO1_2_12") (pintype "bidirectional"))
    )
    (net (code "35") (name "MB_OUT2") (class "Default")
      (node (ref "MOTOR_B") (pin "2") (pinfunction "2_2") (pintype "bidirectional"))
      (node (ref "MOTOR_CTL") (pin "7") (pinfunction "BO2_1_7") (pintype "bidirectional"))
      (node (ref "MOTOR_CTL") (pin "8") (pinfunction "BO2_2_8") (pintype "bidirectional"))
    )
    (net (code "36") (name "MB_PWM") (class "Default")
      (node (ref "MOTOR_CTL") (pin "15") (pinfunction "PWMB_15") (pintype "bidirectional"))
      (node (ref "μC") (pin "14") (pinfunction "PWM1H1/RTCC/RP14/CN12/PMWR/RB14_14") (pintype "bidirectional"))
    )
    (net (code "37") (name "MCLR") (class "Default")
      (node (ref "R12") (pin "1") (pinfunction "1_1") (pintype "passive"))
      (node (ref "UC_PROG") (pin "1") (pinfunction "1_1") (pintype "passive"))
      (node (ref "µC_RST") (pin "2") (pinfunction "COM_1_2") (pintype "bidirectional"))
      (node (ref "µC_RST") (pin "4") (pinfunction "COM_2_4") (pintype "bidirectional"))
      (node (ref "μC") (pin "18") (pinfunction "MCLR_18") (pintype "input"))
    )
    (net (code "38") (name "M_STDBY") (class "Default")
      (node (ref "MOTOR_CTL") (pin "19") (pinfunction "STBY_19") (pintype "bidirectional"))
      (node (ref "μC") (pin "15") (pinfunction "PWM1L1/RP15/CN11/PMCS1/RB15_15") (pintype "bidirectional"))
    )
    (net (code "39") (name "Net-(3.3V-PadA)") (class "Default")
      (node (ref "3.3V") (pin "A") (pinfunction "A_A") (pintype "passive"))
      (node (ref "R3") (pin "2") (pinfunction "2_2") (pintype "passive"))
    )
    (net (code "40") (name "Net-(5V-PadA)") (class "Default")
      (node (ref "5V") (pin "A") (pinfunction "A_A") (pintype "passive"))
      (node (ref "R2") (pin "2") (pinfunction "2_2") (pintype "passive"))
    )
    (net (code "41") (name "Net-(7.4V-PadA)") (class "Default")
      (node (ref "7.4V") (pin "A") (pinfunction "A_A") (pintype "passive"))
      (node (ref "R1") (pin "2") (pinfunction "2_2") (pintype "passive"))
    )
    (net (code "42") (name "Net-(BAT-Pad+)") (class "Default")
      (node (ref "BAT") (pin "+") (pinfunction "+_+") (pintype "power_in"))
      (node (ref "POWER_SW") (pin "3") (pinfunction "3_3") (pintype "bidirectional"))
    )
    (net (code "43") (name "Net-(BT_CON-PadC)") (class "Default")
      (node (ref "BT_CON") (pin "C") (pinfunction "C_C") (pintype "passive"))
      (node (ref "R9") (pin "2") (pinfunction "2_2") (pintype "passive"))
    )
    (net (code "44") (name "Net-(D1-K)") (class "Default")
      (node (ref "D1") (pin "1") (pinfunction "K_1") (pintype "bidirectional"))
      (node (ref "R12") (pin "2") (pinfunction "2_2") (pintype "passive"))
    )
    (net (code "45") (name "Net-(LED1-PadA)") (class "Default")
      (node (ref "LED1") (pin "A") (pinfunction "A_A") (pintype "passive"))
      (node (ref "R4") (pin "2") (pinfunction "2_2") (pintype "passive"))
    )
    (net (code "46") (name "Net-(LED2-PadA)") (class "Default")
      (node (ref "LED2") (pin "A") (pinfunction "A_A") (pintype "passive"))
      (node (ref "R5") (pin "2") (pinfunction "2_2") (pintype "passive"))
    )
    (net (code "47") (name "Net-(LED3-PadA)") (class "Default")
      (node (ref "LED3") (pin "A") (pinfunction "A_A") (pintype "passive"))
      (node (ref "R6") (pin "2") (pinfunction "2_2") (pintype "passive"))
    )
    (net (code "48") (name "Net-(LED4-PadA)") (class "Default")
      (node (ref "LED4") (pin "A") (pinfunction "A_A") (pintype "passive"))
      (node (ref "R7") (pin "2") (pinfunction "2_2") (pintype "passive"))
    )
    (net (code "49") (name "Net-(LED5-PadA)") (class "Default")
      (node (ref "LED5") (pin "A") (pinfunction "A_A") (pintype "passive"))
      (node (ref "R8") (pin "2") (pinfunction "2_2") (pintype "passive"))
    )
    (net (code "50") (name "Net-(S1-COM_1)") (class "Default")
      (node (ref "C23") (pin "1") (pinfunction "1_1") (pintype "passive"))
      (node (ref "R13") (pin "1") (pinfunction "1_1") (pintype "passive"))
      (node (ref "R14") (pin "1") (pinfunction "1_1") (pintype "passive"))
      (node (ref "S1") (pin "2") (pinfunction "COM_1_2") (pintype "bidirectional"))
      (node (ref "S1") (pin "4") (pinfunction "COM_2_4") (pintype "bidirectional"))
    )
    (net (code "51") (name "Net-(μC-AVDD)") (class "Default")
      (node (ref "C11") (pin "2") (pinfunction "2_2") (pintype "passive"))
      (node (ref "C12") (pin "2") (pinfunction "2_2") (pintype "passive"))
      (node (ref "L1") (pin "1") (pinfunction "1_1") (pintype "passive"))
      (node (ref "μC") (pin "17") (pinfunction "AVDD_17") (pintype "power_in"))
    )
    (net (code "52") (name "Net-(μC-VCAP{slash}VDDCORE)") (class "Default")
      (node (ref "C13") (pin "2") (pinfunction "2_2") (pintype "passive"))
      (node (ref "μC") (pin "7") (pinfunction "VCAP/VDDCORE_7") (pintype "power_in"))
    )
    (net (code "53") (name "OSC1") (class "Default")
      (node (ref "C16") (pin "1") (pinfunction "1_1") (pintype "passive"))
      (node (ref "Q1") (pin "1") (pinfunction "1_1") (pintype "passive"))
      (node (ref "μC") (pin "30") (pinfunction "OSC1/CLKI/CN30/RA2_30") (pintype "bidirectional"))
    )
    (net (code "54") (name "OSC2") (class "Default")
      (node (ref "C17") (pin "1") (pinfunction "1_1") (pintype "passive"))
      (node (ref "Q1") (pin "2") (pinfunction "2_2") (pintype "passive"))
      (node (ref "μC") (pin "31") (pinfunction "OSC2/CLKO/CN29/RA3_31") (pintype "bidirectional"))
    )
    (net (code "55") (name "PG_EC3") (class "Default")
      (node (ref "UC_PROG") (pin "5") (pinfunction "5_5") (pintype "passive"))
      (node (ref "μC") (pin "42") (pinfunction "PGEC3/ASCL1/RP6/CN24/PMD6/RB6_42") (pintype "bidirectional"))
    )
    (net (code "56") (name "PG_ED3") (class "Default")
      (node (ref "UC_PROG") (pin "4") (pinfunction "4_4") (pintype "passive"))
      (node (ref "μC") (pin "41") (pinfunction "PGED3/ASDA1/RP5/CN27/PMD7/RB5_41") (pintype "bidirectional"))
    )
    (net (code "57") (name "SENS_DIST_1") (class "Default")
      (node (ref "SENS_DIST_1") (pin "3") (pinfunction "3_3") (pintype "passive"))
      (node (ref "μC") (pin "24") (pinfunction "AN5/C1IN+/RP3/CN7/RB3_24") (pintype "bidirectional"))
    )
    (net (code "58") (name "SENS_DIST_2") (class "Default")
      (node (ref "SENS_DIST_2") (pin "3") (pinfunction "3_3") (pintype "passive"))
      (node (ref "μC") (pin "25") (pinfunction "AN6/RP16/CN8/RC0_25") (pintype "bidirectional"))
    )
    (net (code "59") (name "SENS_DIST_3") (class "Default")
      (node (ref "SENS_DIST_3") (pin "3") (pinfunction "3_3") (pintype "passive"))
      (node (ref "μC") (pin "23") (pinfunction "AN4/C1IN-/RP2/CN6/RB2_23") (pintype "bidirectional"))
    )
    (net (code "60") (name "UART_BT_RX") (class "Default")
      (node (ref "RX_SEL") (pin "1") (pinfunction "1_1") (pintype "passive"))
      (node (ref "UART_BT") (pin "8") (pinfunction "UART_TX_8") (pintype "bidirectional"))
    )
    (net (code "61") (name "UART_DBG_RX") (class "Default")
      (node (ref "RX_SEL") (pin "3") (pinfunction "3_3") (pintype "passive"))
      (node (ref "UART") (pin "1") (pinfunction "1_1") (pintype "passive"))
    )
    (net (code "62") (name "UART_RX") (class "Default")
      (node (ref "RX_SEL") (pin "2") (pinfunction "2_2") (pintype "passive"))
      (node (ref "μC") (pin "37") (pinfunction "RP20/CN25/PMA4/RC4_37") (pintype "bidirectional"))
    )
    (net (code "63") (name "UART_TX") (class "Default")
      (node (ref "UART") (pin "2") (pinfunction "2_2") (pintype "passive"))
      (node (ref "UART_BT") (pin "7") (pinfunction "UART_RX_7") (pintype "bidirectional"))
      (node (ref "μC") (pin "38") (pinfunction "RP21/CN26/PMA3/RC5_38") (pintype "bidirectional"))
    )
    (net (code "64") (name "unconnected-(IMU_1-Pad1)") (class "Default")
      (node (ref "IMU_1") (pin "1") (pinfunction "1_1") (pintype "passive"))
    )
    (net (code "65") (name "unconnected-(IMU_1-Pad2)") (class "Default")
      (node (ref "IMU_1") (pin "2") (pinfunction "2_2") (pintype "passive"))
    )
    (net (code "66") (name "unconnected-(IMU_1-Pad3)") (class "Default")
      (node (ref "IMU_1") (pin "3") (pinfunction "3_3") (pintype "passive"))
    )
    (net (code "67") (name "unconnected-(IMU_1-Pad5)") (class "Default")
      (node (ref "IMU_1") (pin "5") (pinfunction "5_5") (pintype "passive"))
    )
    (net (code "68") (name "unconnected-(IMU_1-Pad6)") (class "Default")
      (node (ref "IMU_1") (pin "6") (pinfunction "6_6") (pintype "passive"))
    )
    (net (code "69") (name "unconnected-(IMU_2-Pad2)") (class "Default")
      (node (ref "IMU_2") (pin "2") (pinfunction "2_2") (pintype "passive"))
    )
    (net (code "70") (name "unconnected-(POWER_SW-Pad1)") (class "Default")
      (node (ref "POWER_SW") (pin "1") (pinfunction "1_1") (pintype "bidirectional"))
    )
    (net (code "71") (name "unconnected-(UART_BT-NC-Pad1)") (class "Default")
      (node (ref "UART_BT") (pin "1") (pinfunction "NC_1") (pintype "no_connect"))
    )
    (net (code "72") (name "unconnected-(UART_BT-P0_0-Pad11)") (class "Default")
      (node (ref "UART_BT") (pin "11") (pinfunction "P0_0_11") (pintype "bidirectional"))
    )
    (net (code "73") (name "unconnected-(UART_BT-P1_2-Pad3)") (class "Default")
      (node (ref "UART_BT") (pin "3") (pinfunction "P1_2_3") (pintype "bidirectional"))
    )
    (net (code "74") (name "unconnected-(UART_BT-P1_3-Pad4)") (class "Default")
      (node (ref "UART_BT") (pin "4") (pinfunction "P1_3_4") (pintype "bidirectional"))
    )
    (net (code "75") (name "unconnected-(UART_BT-P1_6-Pad6)") (class "Default")
      (node (ref "UART_BT") (pin "6") (pinfunction "P1_6_6") (pintype "bidirectional"))
    )
    (net (code "76") (name "unconnected-(UART_BT-P1_7-Pad5)") (class "Default")
      (node (ref "UART_BT") (pin "5") (pinfunction "P1_7_5") (pintype "bidirectional"))
    )
    (net (code "77") (name "unconnected-(UART_BT-P2_7-Pad15)") (class "Default")
      (node (ref "UART_BT") (pin "15") (pinfunction "P2_7_15") (pintype "bidirectional"))
    )
    (net (code "78") (name "unconnected-(UART_BT-P3_6-Pad9)") (class "Default")
      (node (ref "UART_BT") (pin "9") (pinfunction "P3_6_9") (pintype "bidirectional"))
    )
    (net (code "79") (name "unconnected-(UC_PROG-Pad6)") (class "Default")
      (node (ref "UC_PROG") (pin "6") (pinfunction "6_6") (pintype "passive"))
    )
  )
)
